# ST25DV64K-JFR6D3.net
KiCad netlist of a schematic drawn in Altium Designer
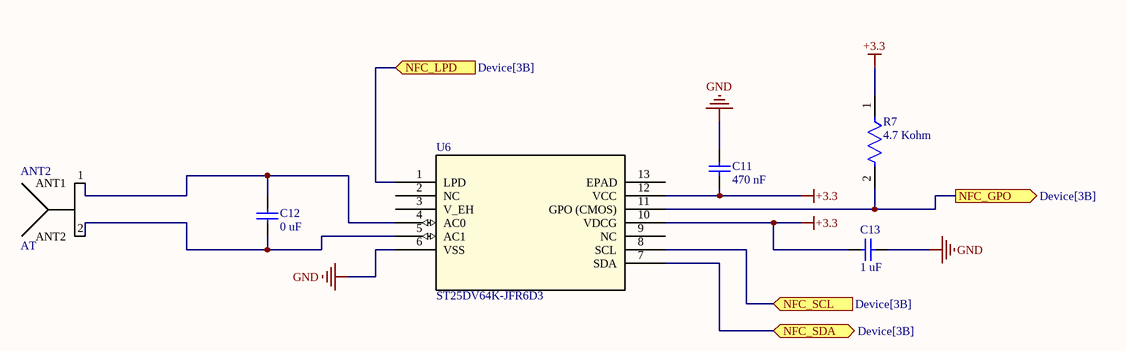
[diagram p0: ST25DV64K-JFR6D3.SchDoc]

(export (version "E")
  (design (tool "Eeschema 10.0.6"))
  (components
    (comp (ref "ANT2") (value "AT") (footprint "AC") (libsource (lib "ANT") (part "AT")))
    (comp (ref "C11")
      (value "470 nF")
      (footprint "CAPC1005X55X25NL05T10")
      (fields (field (name "MANUFACTURER") "Murata") (field (name "PART NUMBER") "GRM155F50J684ZE01D"))
      (libsource (lib "Altium Content Vault") (part "CAP"))
    )
    (comp (ref "C12")
      (value "0 uF")
      (footprint "CAPC1005X55X25NL05T10")
      (fields (field (name "MANUFACTURER") "Murata") (field (name "PART NUMBER") "GRM155F50J684ZE01D"))
      (libsource (lib "Altium Content Vault") (part "CAP"))
    )
    (comp (ref "C13")
      (value "1 uF")
      (footprint "CAPC1005X55X25NL05T10")
      (fields (field (name "MANUFACTURER") "Murata") (field (name "PART NUMBER") "GRM155F50J684ZE01D"))
      (libsource (lib "Altium Content Vault") (part "CAP"))
    )
    (comp (ref "R7")
      (value "4.7 Kohm")
      (footprint "FP-RC1005-IPC_C")
      (description "Res Thick Film 0402 1.87kΩ 1% 0.063W ±100ppm/°C Molded SMD T/R")
      (fields (field (name "TOLERANCE") "1%"))
      (libsource (lib "Altium Content Vault") (part "1029c3af85768c4190bb7ad29bc67b5"))
    )
    (comp (ref "U6")
      (value "ST25DV64K-JFR6D3")
      (footprint "UFDFPN12_3X3_STM")
      (fields (field (name "COPYRIGHT") "Copyright (C) 2023 Ultra Librarian. All rights reserved."))
      (libsource (lib "ANT") (part "ST25DV64K-JFR6D3"))
    )
  )
  (nets
    (net (code "1") (name "+3.3") (class "Default")
      (node (ref "C11") (pin "2") (pinfunction "2_2") (pintype "passive"))
      (node (ref "C13") (pin "1") (pinfunction "1_1") (pintype "passive"))
      (node (ref "R7") (pin "1") (pinfunction "1_1") (pintype "passive"))
      (node (ref "U6") (pin "10") (pinfunction "VDCG_10") (pintype "passive"))
      (node (ref "U6") (pin "12") (pinfunction "VCC_12") (pintype "power_in"))
    )
    (net (code "2") (name "/NFC_GPO") (class "Default")
      (node (ref "R7") (pin "2") (pinfunction "2_2") (pintype "passive"))
      (node (ref "U6") (pin "11") (pinfunction "GPO_(CMOS)_11") (pintype "passive"))
    )
    (net (code "3") (name "/NFC_LPD") (class "Default")
      (node (ref "U6") (pin "1") (pinfunction "LPD_1") (pintype "passive"))
    )
    (net (code "4") (name "/NFC_SCL") (class "Default")
      (node (ref "U6") (pin "8") (pinfunction "SCL_8") (pintype "passive"))
    )
    (net (code "5") (name "/NFC_SDA") (class "Default")
      (node (ref "U6") (pin "7") (pinfunction "SDA_7") (pintype "passive"))
    )
    (net (code "6") (name "GND") (class "Default")
      (node (ref "C11") (pin "1") (pinfunction "1_1") (pintype "passive"))
      (node (ref "C13") (pin "2") (pinfunction "2_2") (pintype "passive"))
      (node (ref "U6") (pin "6") (pinfunction "VSS_6") (pintype "passive"))
    )
    (net (code "7") (name "Net-(ANT2-ANT1)") (class "Default")
      (node (ref "ANT2") (pin "1") (pinfunction "ANT1_1") (pintype "passive"))
      (node (ref "C12") (pin "1") (pinfunction "1_1") (pintype "passive"))
      (node (ref "U6") (pin "4") (pinfunction "AC0_4") (pintype "bidirectional"))
    )
    (net (code "8") (name "Net-(ANT2-ANT2)") (class "Default")
      (node (ref "ANT2") (pin "2") (pinfunction "ANT2_2") (pintype "passive"))
      (node (ref "C12") (pin "2") (pinfunction "2_2") (pintype "passive"))
      (node (ref "U6") (pin "5") (pinfunction "AC1_5") (pintype "bidirectional"))
    )
    (net (code "9") (name "unconnected-(U6-EPAD-Pad13)") (class "Default")
      (node (ref "U6") (pin "13") (pinfunction "EPAD_13") (pintype "passive"))
    )
    (net (code "10") (name "unconnected-(U6-NC-Pad2)") (class "Default")
      (node (ref "U6") (pin "2") (pinfunction "NC_2") (pintype "passive"))
    )
    (net (code "11") (name "unconnected-(U6-NC-Pad9)") (class "Default")
      (node (ref "U6") (pin "9") (pinfunction "NC_9") (pintype "passive"))
    )
    (net (code "12") (name "unconnected-(U6-V_EH-Pad3)") (class "Default")
      (node (ref "U6") (pin "3") (pinfunction "V_EH_3") (pintype "passive"))
    )
  )
)
